# 6502_cable_ada.net
KiCad netlist of a schematic drawn in EAGLE
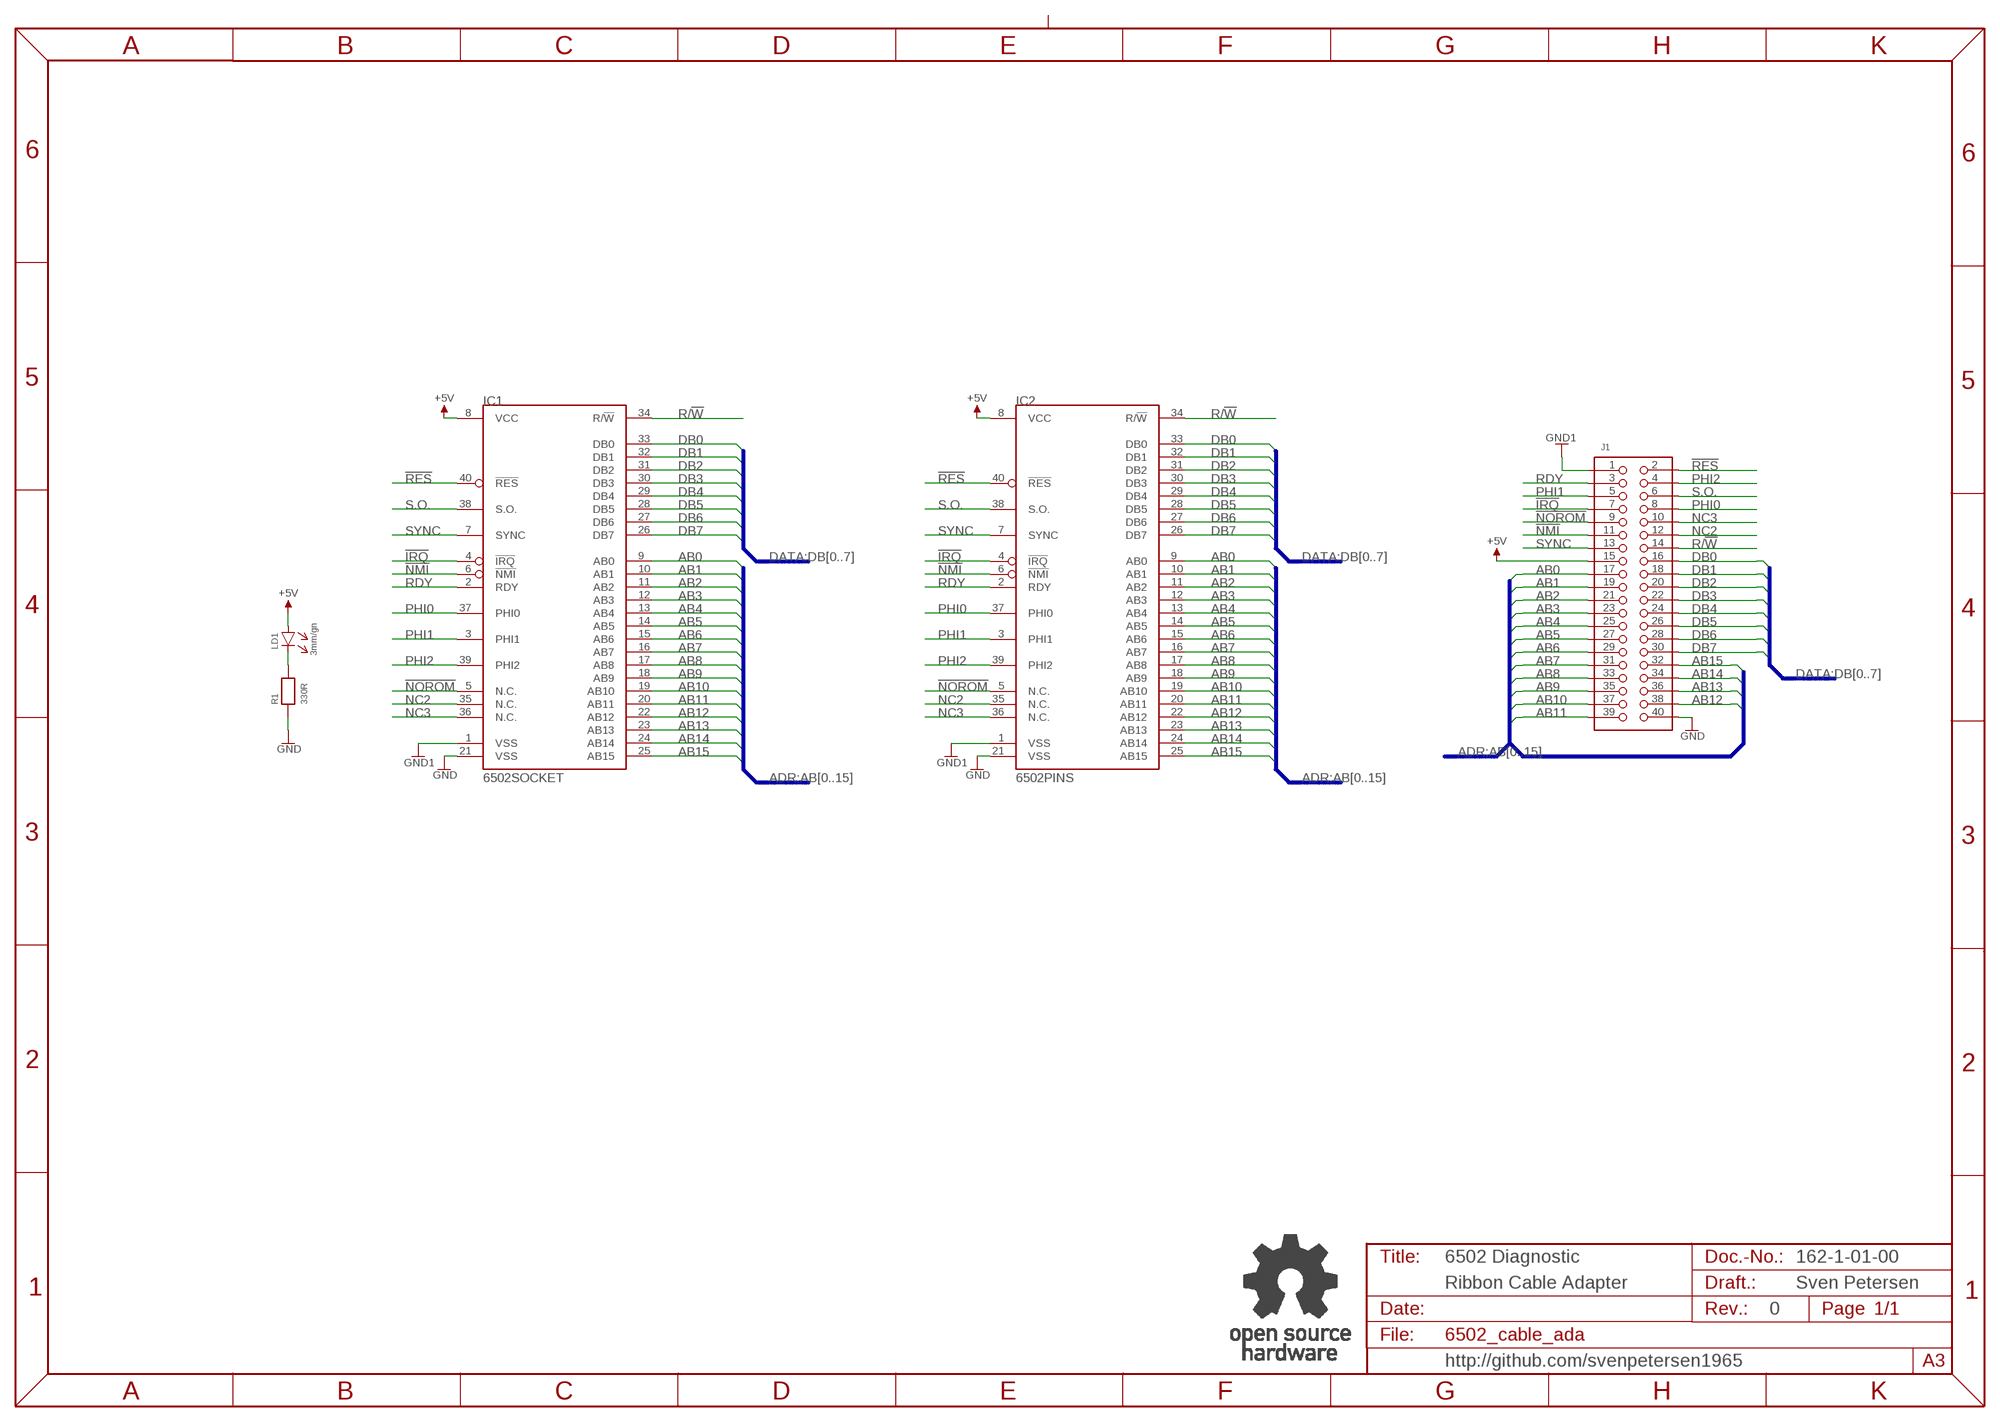
[diagram p0: schematic, sheet 1]

(export (version "E")
  (design (tool "Eeschema 10.0.6"))
  (components
    (comp (ref "IC1")
      (value "6502SOCKET")
      (footprint "eagle-import:GS40P")
      (libsource (lib "eagle-import") (part "6502SOCKET"))
    )
    (comp (ref "IC2")
      (value "6502PINS")
      (footprint "eagle-import:DIL40_PINS_SS")
      (libsource (lib "eagle-import") (part "6502PINS"))
    )
    (comp (ref "J1")
      (value "PINHD-2X20WV")
      (footprint "eagle-import:2X20WV")
      (libsource (lib "eagle-import") (part "PINHD-2X20WV"))
    )
    (comp (ref "LD1")
      (value "3mm/gn")
      (footprint "eagle-import:3MM")
      (libsource (lib "eagle-import") (part "3MM"))
    )
    (comp (ref "R1")
      (value "330R")
      (footprint "eagle-import:R-10")
      (libsource (lib "eagle-import") (part "RES04"))
    )
    (comp (ref "U$11")
      (value "OPEN_SOURCE_HW")
      (footprint "eagle-import:OPENHW")
      (libsource (lib "eagle-import") (part "OPEN_SOURCE_HW"))
    )
  )
  (nets
    (net (code "25") (name "+5V") (class "Default")
      (node (ref "IC1") (pin "8") (pinfunction "VCC_8") (pintype "power_in"))
      (node (ref "IC2") (pin "8") (pinfunction "VCC_8") (pintype "power_in"))
      (node (ref "J1") (pin "15") (pinfunction "15_15") (pintype "passive"))
      (node (ref "LD1") (pin "A") (pinfunction "A_A") (pintype "bidirectional"))
    )
    (net (code "26") (name "/AB0") (class "Default")
      (node (ref "IC1") (pin "9") (pinfunction "AB0_9") (pintype "output"))
      (node (ref "IC2") (pin "9") (pinfunction "AB0_9") (pintype "output"))
      (node (ref "J1") (pin "17") (pinfunction "17_17") (pintype "passive"))
    )
    (net (code "27") (name "/AB1") (class "Default")
      (node (ref "IC1") (pin "10") (pinfunction "AB1_10") (pintype "output"))
      (node (ref "IC2") (pin "10") (pinfunction "AB1_10") (pintype "output"))
      (node (ref "J1") (pin "19") (pinfunction "19_19") (pintype "passive"))
    )
    (net (code "28") (name "/AB2") (class "Default")
      (node (ref "IC1") (pin "11") (pinfunction "AB2_11") (pintype "output"))
      (node (ref "IC2") (pin "11") (pinfunction "AB2_11") (pintype "output"))
      (node (ref "J1") (pin "21") (pinfunction "21_21") (pintype "passive"))
    )
    (net (code "29") (name "/AB3") (class "Default")
      (node (ref "IC1") (pin "12") (pinfunction "AB3_12") (pintype "output"))
      (node (ref "IC2") (pin "12") (pinfunction "AB3_12") (pintype "output"))
      (node (ref "J1") (pin "23") (pinfunction "23_23") (pintype "passive"))
    )
    (net (code "30") (name "/AB4") (class "Default")
      (node (ref "IC1") (pin "13") (pinfunction "AB4_13") (pintype "output"))
      (node (ref "IC2") (pin "13") (pinfunction "AB4_13") (pintype "output"))
      (node (ref "J1") (pin "25") (pinfunction "25_25") (pintype "passive"))
    )
    (net (code "31") (name "/AB5") (class "Default")
      (node (ref "IC1") (pin "14") (pinfunction "AB5_14") (pintype "output"))
      (node (ref "IC2") (pin "14") (pinfunction "AB5_14") (pintype "output"))
      (node (ref "J1") (pin "27") (pinfunction "27_27") (pintype "passive"))
    )
    (net (code "32") (name "/AB6") (class "Default")
      (node (ref "IC1") (pin "15") (pinfunction "AB6_15") (pintype "output"))
      (node (ref "IC2") (pin "15") (pinfunction "AB6_15") (pintype "output"))
      (node (ref "J1") (pin "29") (pinfunction "29_29") (pintype "passive"))
    )
    (net (code "33") (name "/AB7") (class "Default")
      (node (ref "IC1") (pin "16") (pinfunction "AB7_16") (pintype "output"))
      (node (ref "IC2") (pin "16") (pinfunction "AB7_16") (pintype "output"))
      (node (ref "J1") (pin "31") (pinfunction "31_31") (pintype "passive"))
    )
    (net (code "34") (name "/AB8") (class "Default")
      (node (ref "IC1") (pin "17") (pinfunction "AB8_17") (pintype "output"))
      (node (ref "IC2") (pin "17") (pinfunction "AB8_17") (pintype "output"))
      (node (ref "J1") (pin "33") (pinfunction "33_33") (pintype "passive"))
    )
    (net (code "35") (name "/AB9") (class "Default")
      (node (ref "IC1") (pin "18") (pinfunction "AB9_18") (pintype "output"))
      (node (ref "IC2") (pin "18") (pinfunction "AB9_18") (pintype "output"))
      (node (ref "J1") (pin "35") (pinfunction "35_35") (pintype "passive"))
    )
    (net (code "36") (name "/AB10") (class "Default")
      (node (ref "IC1") (pin "19") (pinfunction "AB10_19") (pintype "output"))
      (node (ref "IC2") (pin "19") (pinfunction "AB10_19") (pintype "output"))
      (node (ref "J1") (pin "37") (pinfunction "37_37") (pintype "passive"))
    )
    (net (code "37") (name "/AB11") (class "Default")
      (node (ref "IC1") (pin "20") (pinfunction "AB11_20") (pintype "output"))
      (node (ref "IC2") (pin "20") (pinfunction "AB11_20") (pintype "output"))
      (node (ref "J1") (pin "39") (pinfunction "39_39") (pintype "passive"))
    )
    (net (code "38") (name "/AB12") (class "Default")
      (node (ref "IC1") (pin "22") (pinfunction "AB12_22") (pintype "output"))
      (node (ref "IC2") (pin "22") (pinfunction "AB12_22") (pintype "output"))
      (node (ref "J1") (pin "38") (pinfunction "38_38") (pintype "passive"))
    )
    (net (code "39") (name "/AB13") (class "Default")
      (node (ref "IC1") (pin "23") (pinfunction "AB13_23") (pintype "output"))
      (node (ref "IC2") (pin "23") (pinfunction "AB13_23") (pintype "output"))
      (node (ref "J1") (pin "36") (pinfunction "36_36") (pintype "passive"))
    )
    (net (code "40") (name "/AB14") (class "Default")
      (node (ref "IC1") (pin "24") (pinfunction "AB14_24") (pintype "output"))
      (node (ref "IC2") (pin "24") (pinfunction "AB14_24") (pintype "output"))
      (node (ref "J1") (pin "34") (pinfunction "34_34") (pintype "passive"))
    )
    (net (code "41") (name "/AB15") (class "Default")
      (node (ref "IC1") (pin "25") (pinfunction "AB15_25") (pintype "output"))
      (node (ref "IC2") (pin "25") (pinfunction "AB15_25") (pintype "output"))
      (node (ref "J1") (pin "32") (pinfunction "32_32") (pintype "passive"))
    )
    (net (code "44") (name "/DB0") (class "Default")
      (node (ref "IC1") (pin "33") (pinfunction "DB0_33") (pintype "bidirectional"))
      (node (ref "IC2") (pin "33") (pinfunction "DB0_33") (pintype "bidirectional"))
      (node (ref "J1") (pin "16") (pinfunction "16_16") (pintype "passive"))
    )
    (net (code "45") (name "/DB1") (class "Default")
      (node (ref "IC1") (pin "32") (pinfunction "DB1_32") (pintype "bidirectional"))
      (node (ref "IC2") (pin "32") (pinfunction "DB1_32") (pintype "bidirectional"))
      (node (ref "J1") (pin "18") (pinfunction "18_18") (pintype "passive"))
    )
    (net (code "46") (name "/DB2") (class "Default")
      (node (ref "IC1") (pin "31") (pinfunction "DB2_31") (pintype "bidirectional"))
      (node (ref "IC2") (pin "31") (pinfunction "DB2_31") (pintype "bidirectional"))
      (node (ref "J1") (pin "20") (pinfunction "20_20") (pintype "passive"))
    )
    (net (code "47") (name "/DB3") (class "Default")
      (node (ref "IC1") (pin "30") (pinfunction "DB3_30") (pintype "bidirectional"))
      (node (ref "IC2") (pin "30") (pinfunction "DB3_30") (pintype "bidirectional"))
      (node (ref "J1") (pin "22") (pinfunction "22_22") (pintype "passive"))
    )
    (net (code "48") (name "/DB4") (class "Default")
      (node (ref "IC1") (pin "29") (pinfunction "DB4_29") (pintype "bidirectional"))
      (node (ref "IC2") (pin "29") (pinfunction "DB4_29") (pintype "bidirectional"))
      (node (ref "J1") (pin "24") (pinfunction "24_24") (pintype "passive"))
    )
    (net (code "49") (name "/DB5") (class "Default")
      (node (ref "IC1") (pin "28") (pinfunction "DB5_28") (pintype "bidirectional"))
      (node (ref "IC2") (pin "28") (pinfunction "DB5_28") (pintype "bidirectional"))
      (node (ref "J1") (pin "26") (pinfunction "26_26") (pintype "passive"))
    )
    (net (code "50") (name "/DB6") (class "Default")
      (node (ref "IC1") (pin "27") (pinfunction "DB6_27") (pintype "bidirectional"))
      (node (ref "IC2") (pin "27") (pinfunction "DB6_27") (pintype "bidirectional"))
      (node (ref "J1") (pin "28") (pinfunction "28_28") (pintype "passive"))
    )
    (net (code "51") (name "/DB7") (class "Default")
      (node (ref "IC1") (pin "26") (pinfunction "DB7_26") (pintype "bidirectional"))
      (node (ref "IC2") (pin "26") (pinfunction "DB7_26") (pintype "bidirectional"))
      (node (ref "J1") (pin "30") (pinfunction "30_30") (pintype "passive"))
    )
    (net (code "52") (name "/NC2") (class "Default")
      (node (ref "IC1") (pin "35") (pinfunction "N.C._35") (pintype "passive"))
      (node (ref "IC2") (pin "35") (pinfunction "N.C._35") (pintype "passive"))
      (node (ref "J1") (pin "12") (pinfunction "12_12") (pintype "passive"))
    )
    (net (code "53") (name "/NC3") (class "Default")
      (node (ref "IC1") (pin "36") (pinfunction "N.C._36") (pintype "passive"))
      (node (ref "IC2") (pin "36") (pinfunction "N.C._36") (pintype "passive"))
      (node (ref "J1") (pin "10") (pinfunction "10_10") (pintype "passive"))
    )
    (net (code "54") (name "/PHI0") (class "Default")
      (node (ref "IC1") (pin "37") (pinfunction "PHI0_37") (pintype "input"))
      (node (ref "IC2") (pin "37") (pinfunction "PHI0_37") (pintype "input"))
      (node (ref "J1") (pin "8") (pinfunction "8_8") (pintype "passive"))
    )
    (net (code "55") (name "/PHI1") (class "Default")
      (node (ref "IC1") (pin "3") (pinfunction "PHI1_3") (pintype "output"))
      (node (ref "IC2") (pin "3") (pinfunction "PHI1_3") (pintype "output"))
      (node (ref "J1") (pin "5") (pinfunction "5_5") (pintype "passive"))
    )
    (net (code "56") (name "/PHI2") (class "Default")
      (node (ref "IC1") (pin "39") (pinfunction "PHI2_39") (pintype "output"))
      (node (ref "IC2") (pin "39") (pinfunction "PHI2_39") (pintype "output"))
      (node (ref "J1") (pin "4") (pinfunction "4_4") (pintype "passive"))
    )
    (net (code "57") (name "/RDY") (class "Default")
      (node (ref "IC1") (pin "2") (pinfunction "RDY_2") (pintype "input"))
      (node (ref "IC2") (pin "2") (pinfunction "RDY_2") (pintype "input"))
      (node (ref "J1") (pin "3") (pinfunction "3_3") (pintype "passive"))
    )
    (net (code "58") (name "/R{slash}~{W}") (class "Default")
      (node (ref "IC1") (pin "34") (pinfunction "R/~{W}_34") (pintype "output"))
      (node (ref "IC2") (pin "34") (pinfunction "R/~{W}_34") (pintype "output"))
      (node (ref "J1") (pin "14") (pinfunction "14_14") (pintype "passive"))
    )
    (net (code "59") (name "/S.O.") (class "Default")
      (node (ref "IC1") (pin "38") (pinfunction "S.O._38") (pintype "input"))
      (node (ref "IC2") (pin "38") (pinfunction "S.O._38") (pintype "input"))
      (node (ref "J1") (pin "6") (pinfunction "6_6") (pintype "passive"))
    )
    (net (code "60") (name "/SYNC") (class "Default")
      (node (ref "IC1") (pin "7") (pinfunction "SYNC_7") (pintype "output"))
      (node (ref "IC2") (pin "7") (pinfunction "SYNC_7") (pintype "output"))
      (node (ref "J1") (pin "13") (pinfunction "13_13") (pintype "passive"))
    )
    (net (code "61") (name "/~{IRQ}") (class "Default")
      (node (ref "IC1") (pin "4") (pinfunction "~{IRQ}_4") (pintype "input"))
      (node (ref "IC2") (pin "4") (pinfunction "~{IRQ}_4") (pintype "input"))
      (node (ref "J1") (pin "7") (pinfunction "7_7") (pintype "passive"))
    )
    (net (code "62") (name "/~{NMI}") (class "Default")
      (node (ref "IC1") (pin "6") (pinfunction "~{NMI}_6") (pintype "input"))
      (node (ref "IC2") (pin "6") (pinfunction "~{NMI}_6") (pintype "input"))
      (node (ref "J1") (pin "11") (pinfunction "11_11") (pintype "passive"))
    )
    (net (code "63") (name "/~{NOROM}") (class "Default")
      (node (ref "IC1") (pin "5") (pinfunction "N.C._5") (pintype "passive"))
      (node (ref "IC2") (pin "5") (pinfunction "N.C._5") (pintype "passive"))
      (node (ref "J1") (pin "9") (pinfunction "9_9") (pintype "passive"))
    )
    (net (code "64") (name "/~{RES}") (class "Default")
      (node (ref "IC1") (pin "40") (pinfunction "~{RES}_40") (pintype "input"))
      (node (ref "IC2") (pin "40") (pinfunction "~{RES}_40") (pintype "input"))
      (node (ref "J1") (pin "2") (pinfunction "2_2") (pintype "passive"))
    )
    (net (code "65") (name "GND") (class "Default")
      (node (ref "IC1") (pin "21") (pinfunction "VSS_21") (pintype "power_in"))
      (node (ref "IC2") (pin "21") (pinfunction "VSS_21") (pintype "power_in"))
      (node (ref "J1") (pin "40") (pinfunction "40_40") (pintype "passive"))
      (node (ref "R1") (pin "1") (pinfunction "1_1") (pintype "passive"))
    )
    (net (code "66") (name "GND1") (class "Default")
      (node (ref "IC1") (pin "1") (pinfunction "VSS_1") (pintype "power_in"))
      (node (ref "IC2") (pin "1") (pinfunction "VSS_1") (pintype "power_in"))
      (node (ref "J1") (pin "1") (pinfunction "1_1") (pintype "passive"))
    )
    (net (code "67") (name "Net-(LD1-K)") (class "Default")
      (node (ref "LD1") (pin "C") (pinfunction "K_C") (pintype "bidirectional"))
      (node (ref "R1") (pin "2") (pinfunction "2_2") (pintype "passive"))
    )
  )
)
